# MS4525DO_GH1_25.net
KiCad netlist of a schematic drawn in Altium Designer
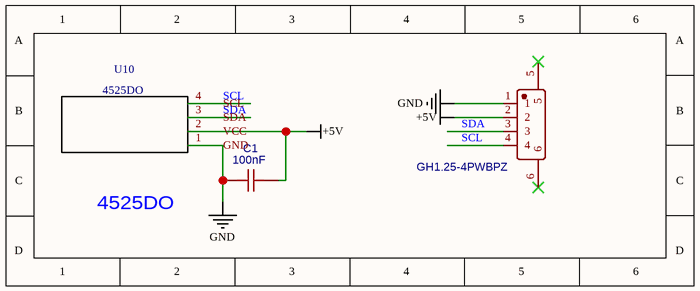
[diagram p0: MS4525DO GH1.25.schdoc]

(export (version "E")
  (design (tool "Eeschema 10.0.6"))
  (components
    (comp (ref "C1")
      (value "100nF")
      (fields (field (name "MANUFACTURER") "SAMSUNG") (field (name "MANUFACTURER PART") "CL10B104KC8NNNC"))
      (libsource (lib "altium-import") (part "root_0_100nF_"))
    )
    (comp (ref "U4")
      (value "GH1.25-4PWBPZ")
      (fields (field (name "MANUFACTURER") "BOOMELE(博穆精密)") (field (name "CONTRIBUTOR") "LCSC"))
      (libsource (lib "altium-import") (part "root_0_GH1.25-4PWBPZ_"))
    )
    (comp (ref "U10") (value "4525DO") (libsource (lib "altium-import") (part "root_0_4525DO_")))
  )
  (nets
    (net (code "1") (name "+5V") (class "Default")
      (node (ref "C1") (pin "2") (pinfunction "2_2") (pintype "passive"))
      (node (ref "U10") (pin "2") (pinfunction "VCC_2") (pintype "passive"))
      (node (ref "U4") (pin "2") (pinfunction "2_2") (pintype "passive"))
    )
    (net (code "2") (name "/SCL") (class "Default")
      (node (ref "U10") (pin "4") (pinfunction "SCL_4") (pintype "passive"))
      (node (ref "U4") (pin "4") (pinfunction "4_4") (pintype "passive"))
    )
    (net (code "3") (name "/SDA") (class "Default")
      (node (ref "U10") (pin "3") (pinfunction "SDA_3") (pintype "passive"))
      (node (ref "U4") (pin "3") (pinfunction "3_3") (pintype "passive"))
    )
    (net (code "4") (name "GND") (class "Default")
      (node (ref "C1") (pin "1") (pinfunction "1_1") (pintype "passive"))
      (node (ref "U10") (pin "1") (pinfunction "GND_1") (pintype "passive"))
      (node (ref "U4") (pin "1") (pinfunction "1_1") (pintype "passive"))
    )
    (net (code "5") (name "unconnected-(U4-Pad5)") (class "Default")
      (node (ref "U4") (pin "5") (pinfunction "5_5") (pintype "passive+no_connect"))
    )
    (net (code "6") (name "unconnected-(U4-Pad6)") (class "Default")
      (node (ref "U4") (pin "6") (pinfunction "6_6") (pintype "passive+no_connect"))
    )
  )
)
